# Remote.net
KiCad netlist of a schematic drawn in Altium Designer
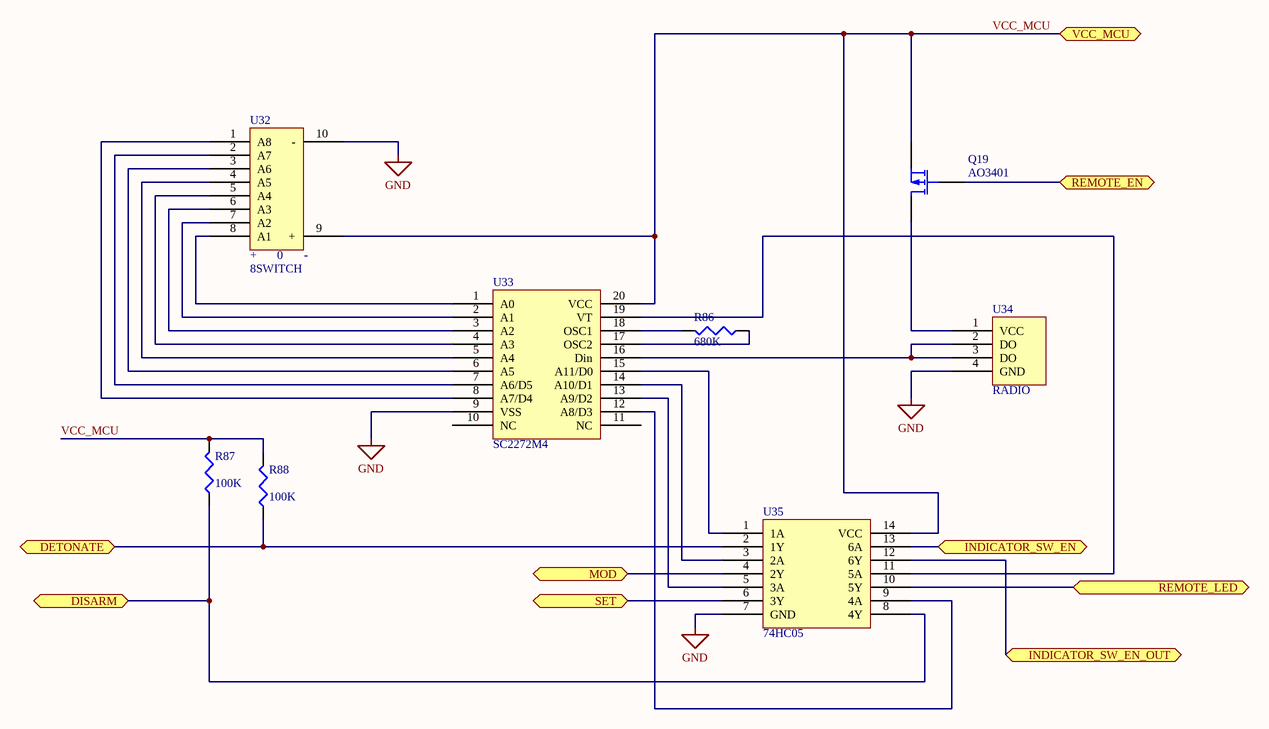
[diagram p0: Remote.SchDoc]

(export (version "E")
  (design (tool "Eeschema 10.0.6"))
  (components
    (comp (ref "Q19")
      (value "AO3401")
      (footprint "clock:SOT23-3-PMOS")
      (description "P-Channel MOSFET")
      (fields (field (name "PUBLISHER") "Altium Limited"))
      (libsource (lib "Miscellaneous Devices") (part "MOSFET-P"))
    )
    (comp (ref "R86")
      (value "680K")
      (footprint "clock:0603")
      (description "Resistor")
      (fields (field (name "Comment") "Res3") (field (name "PUBLISHER") "Altium Limited"))
      (libsource (lib "Miscellaneous Devices") (part "Res3"))
    )
    (comp (ref "R87")
      (value "100K")
      (footprint "clock:0603")
      (description "Resistor")
      (fields (field (name "Comment") "Res3") (field (name "PUBLISHER") "Altium Limited"))
      (libsource (lib "Miscellaneous Devices") (part "Res3"))
    )
    (comp (ref "R88")
      (value "100K")
      (footprint "clock:0603")
      (description "Resistor")
      (fields (field (name "Comment") "Res3") (field (name "PUBLISHER") "Altium Limited"))
      (libsource (lib "Miscellaneous Devices") (part "Res3"))
    )
    (comp (ref "U32")
      (value "8SWITCH")
      (footprint "clock:DSDT08LSGET")
      (libsource (lib "clock") (part "8SWITCH"))
    )
    (comp (ref "U33")
      (value "SC2272M4")
      (footprint "clock:WSO20_M")
      (libsource (lib "clock") (part "SC2272M4"))
    )
    (comp (ref "U34") (value "RADIO") (footprint "clock:RADIO") (libsource (lib "clock") (part "RADIO")))
    (comp (ref "U35") (value "74HC05") (footprint "TSSOP14") (libsource (lib "clock") (part "74HC05")))
  )
  (nets
    (net (code "1") (name "/DETONATE") (class "Default")
      (node (ref "R88") (pin "1") (pinfunction "1_1") (pintype "passive"))
      (node (ref "U35") (pin "2") (pinfunction "1Y_2") (pintype "passive"))
    )
    (net (code "2") (name "/DISARM") (class "Default")
      (node (ref "R87") (pin "1") (pinfunction "1_1") (pintype "passive"))
      (node (ref "U35") (pin "8") (pinfunction "4Y_8") (pintype "passive"))
    )
    (net (code "3") (name "/INDICATOR_SW_EN") (class "Default")
      (node (ref "U35") (pin "13") (pinfunction "6A_13") (pintype "passive"))
    )
    (net (code "4") (name "/INDICATOR_SW_EN_OUT") (class "Default")
      (node (ref "U35") (pin "12") (pinfunction "6Y_12") (pintype "passive"))
    )
    (net (code "5") (name "/MOD") (class "Default")
      (node (ref "U35") (pin "4") (pinfunction "2Y_4") (pintype "passive"))
    )
    (net (code "6") (name "/REMOTE_EN") (class "Default")
      (node (ref "Q19") (pin "2") (pinfunction "G_2") (pintype "passive"))
    )
    (net (code "7") (name "/REMOTE_LED") (class "Default")
      (node (ref "U35") (pin "10") (pinfunction "5Y_10") (pintype "passive"))
    )
    (net (code "8") (name "/SET") (class "Default")
      (node (ref "U35") (pin "6") (pinfunction "3Y_6") (pintype "passive"))
    )
    (net (code "9") (name "/VCC_MCU") (class "Default")
      (node (ref "Q19") (pin "3") (pinfunction "S_3") (pintype "passive"))
      (node (ref "R87") (pin "2") (pinfunction "2_2") (pintype "passive"))
      (node (ref "R88") (pin "2") (pinfunction "2_2") (pintype "passive"))
      (node (ref "U32") (pin "9") (pinfunction "+_9") (pintype "passive"))
      (node (ref "U33") (pin "20") (pinfunction "VCC_20") (pintype "passive"))
      (node (ref "U35") (pin "14") (pinfunction "VCC_14") (pintype "passive"))
    )
    (net (code "10") (name "GND") (class "Default")
      (node (ref "U32") (pin "10") (pinfunction "-_10") (pintype "passive"))
      (node (ref "U33") (pin "9") (pinfunction "VSS_9") (pintype "passive"))
      (node (ref "U34") (pin "4") (pinfunction "GND_4") (pintype "passive"))
      (node (ref "U35") (pin "7") (pinfunction "GND_7") (pintype "passive"))
    )
    (net (code "11") (name "Net-(Q19-D)") (class "Default")
      (node (ref "Q19") (pin "1") (pinfunction "D_1") (pintype "passive"))
      (node (ref "U34") (pin "1") (pinfunction "VCC_1") (pintype "passive"))
    )
    (net (code "12") (name "Net-(U32-A1)") (class "Default")
      (node (ref "U32") (pin "8") (pinfunction "A1_8") (pintype "passive"))
      (node (ref "U33") (pin "1") (pinfunction "A0_1") (pintype "passive"))
    )
    (net (code "13") (name "Net-(U32-A2)") (class "Default")
      (node (ref "U32") (pin "7") (pinfunction "A2_7") (pintype "passive"))
      (node (ref "U33") (pin "2") (pinfunction "A1_2") (pintype "passive"))
    )
    (net (code "14") (name "Net-(U32-A3)") (class "Default")
      (node (ref "U32") (pin "6") (pinfunction "A3_6") (pintype "passive"))
      (node (ref "U33") (pin "3") (pinfunction "A2_3") (pintype "passive"))
    )
    (net (code "15") (name "Net-(U32-A4)") (class "Default")
      (node (ref "U32") (pin "5") (pinfunction "A4_5") (pintype "passive"))
      (node (ref "U33") (pin "4") (pinfunction "A3_4") (pintype "passive"))
    )
    (net (code "16") (name "Net-(U32-A5)") (class "Default")
      (node (ref "U32") (pin "4") (pinfunction "A5_4") (pintype "passive"))
      (node (ref "U33") (pin "5") (pinfunction "A4_5") (pintype "passive"))
    )
    (net (code "17") (name "Net-(U32-A6)") (class "Default")
      (node (ref "U32") (pin "3") (pinfunction "A6_3") (pintype "passive"))
      (node (ref "U33") (pin "6") (pinfunction "A5_6") (pintype "passive"))
    )
    (net (code "18") (name "Net-(U32-A7)") (class "Default")
      (node (ref "U32") (pin "2") (pinfunction "A7_2") (pintype "passive"))
      (node (ref "U33") (pin "7") (pinfunction "A6/D5_7") (pintype "passive"))
    )
    (net (code "19") (name "Net-(U32-A8)") (class "Default")
      (node (ref "U32") (pin "1") (pinfunction "A8_1") (pintype "passive"))
      (node (ref "U33") (pin "8") (pinfunction "A7/D4_8") (pintype "passive"))
    )
    (net (code "20") (name "Net-(U33-A8{slash}D3)") (class "Default")
      (node (ref "U33") (pin "12") (pinfunction "A8/D3_12") (pintype "passive"))
      (node (ref "U35") (pin "9") (pinfunction "4A_9") (pintype "passive"))
    )
    (net (code "21") (name "Net-(U33-A9{slash}D2)") (class "Default")
      (node (ref "U33") (pin "13") (pinfunction "A9/D2_13") (pintype "passive"))
      (node (ref "U35") (pin "5") (pinfunction "3A_5") (pintype "passive"))
    )
    (net (code "22") (name "Net-(U33-A10{slash}D1)") (class "Default")
      (node (ref "U33") (pin "14") (pinfunction "A10/D1_14") (pintype "passive"))
      (node (ref "U35") (pin "3") (pinfunction "2A_3") (pintype "passive"))
    )
    (net (code "23") (name "Net-(U33-A11{slash}D0)") (class "Default")
      (node (ref "U33") (pin "15") (pinfunction "A11/D0_15") (pintype "passive"))
      (node (ref "U35") (pin "1") (pinfunction "1A_1") (pintype "passive"))
    )
    (net (code "24") (name "Net-(U33-Din)") (class "Default")
      (node (ref "U33") (pin "16") (pinfunction "Din_16") (pintype "passive"))
      (node (ref "U34") (pin "2") (pinfunction "DO_2") (pintype "passive"))
      (node (ref "U34") (pin "3") (pinfunction "DO_3") (pintype "passive"))
    )
    (net (code "25") (name "Net-(U33-OSC1)") (class "Default")
      (node (ref "R86") (pin "2") (pinfunction "2_2") (pintype "passive"))
      (node (ref "U33") (pin "18") (pinfunction "OSC1_18") (pintype "passive"))
    )
    (net (code "26") (name "Net-(U33-OSC2)") (class "Default")
      (node (ref "R86") (pin "1") (pinfunction "1_1") (pintype "passive"))
      (node (ref "U33") (pin "17") (pinfunction "OSC2_17") (pintype "passive"))
    )
    (net (code "27") (name "Net-(U33-VT)") (class "Default")
      (node (ref "U33") (pin "19") (pinfunction "VT_19") (pintype "passive"))
      (node (ref "U35") (pin "11") (pinfunction "5A_11") (pintype "passive"))
    )
    (net (code "28") (name "unconnected-(U33-NC-Pad10)") (class "Default")
      (node (ref "U33") (pin "10") (pinfunction "NC_10") (pintype "passive"))
    )
    (net (code "29") (name "unconnected-(U33-NC-Pad11)") (class "Default")
      (node (ref "U33") (pin "11") (pinfunction "NC_11") (pintype "passive"))
    )
  )
)
